# HMI_Board.net
KiCad netlist of a schematic drawn in EAGLE
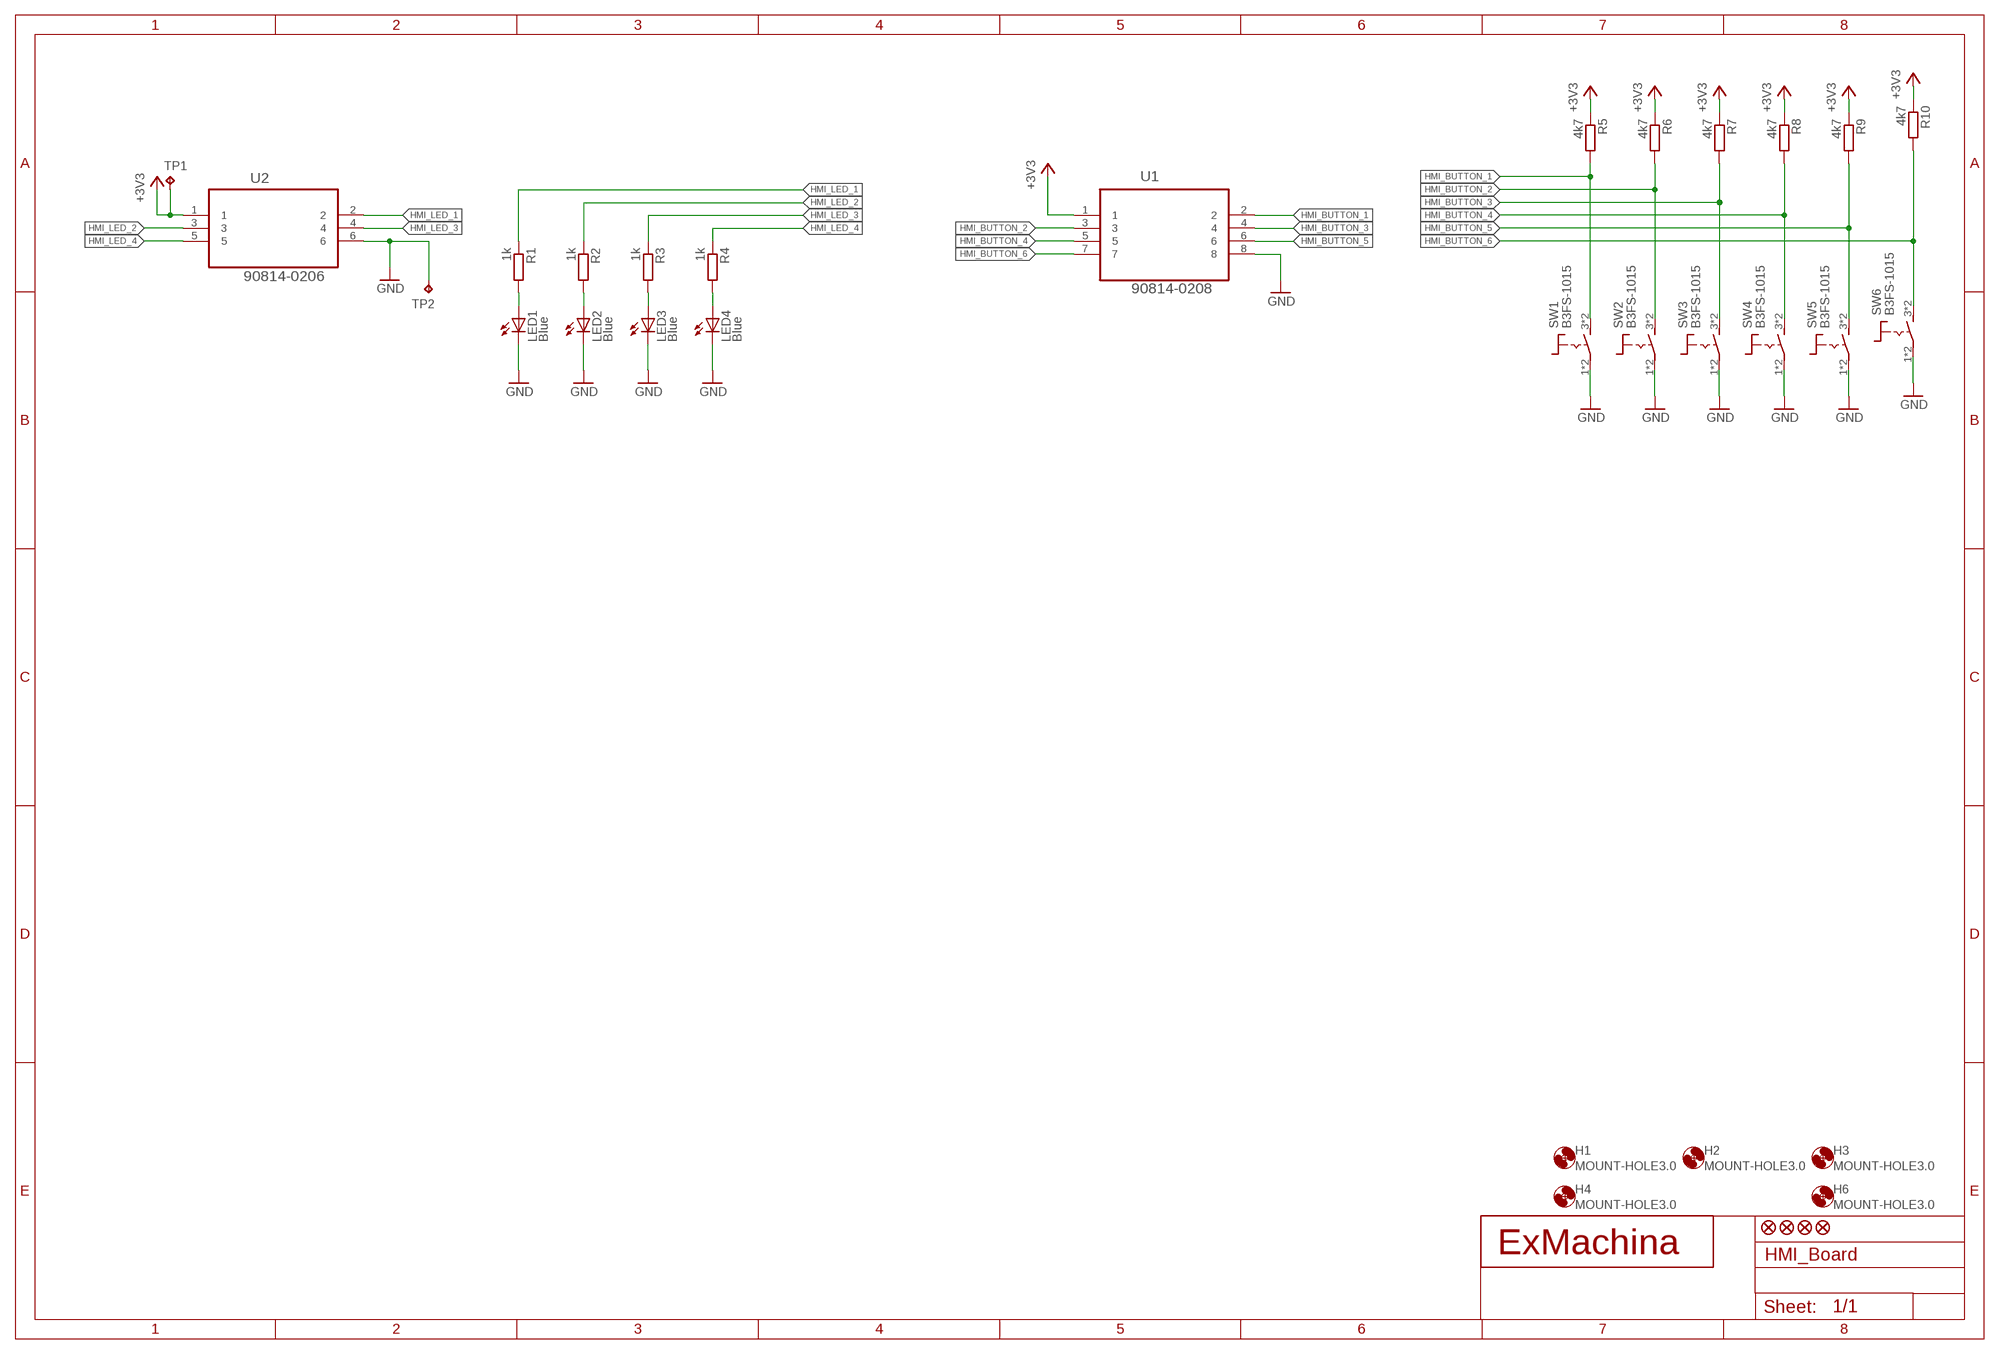
[diagram p0: schematic, sheet 1]

(export (version "E")
  (design (tool "Eeschema 10.0.6"))
  (components
    (comp (ref "H1")
      (value "MOUNT-HOLE3.0")
      (footprint "eagle-import:3,0")
      (libsource (lib "eagle-import") (part "MOUNT-HOLE3.0"))
    )
    (comp (ref "H2")
      (value "MOUNT-HOLE3.0")
      (footprint "eagle-import:3,0")
      (libsource (lib "eagle-import") (part "MOUNT-HOLE3.0"))
    )
    (comp (ref "H3")
      (value "MOUNT-HOLE3.0")
      (footprint "eagle-import:3,0")
      (libsource (lib "eagle-import") (part "MOUNT-HOLE3.0"))
    )
    (comp (ref "H4")
      (value "MOUNT-HOLE3.0")
      (footprint "eagle-import:3,0")
      (libsource (lib "eagle-import") (part "MOUNT-HOLE3.0"))
    )
    (comp (ref "H6")
      (value "MOUNT-HOLE3.0")
      (footprint "eagle-import:3,0")
      (libsource (lib "eagle-import") (part "MOUNT-HOLE3.0"))
    )
    (comp (ref "JP1")
      (value "FIDUCIAL1X2")
      (footprint "eagle-import:FIDUCIAL-1X2")
      (libsource (lib "eagle-import") (part "FIDUCIAL1X2"))
    )
    (comp (ref "JP2")
      (value "FIDUCIAL1X2")
      (footprint "eagle-import:FIDUCIAL-1X2")
      (libsource (lib "eagle-import") (part "FIDUCIAL1X2"))
    )
    (comp (ref "JP3")
      (value "FIDUCIAL1X2")
      (footprint "eagle-import:FIDUCIAL-1X2")
      (libsource (lib "eagle-import") (part "FIDUCIAL1X2"))
    )
    (comp (ref "JP4")
      (value "FIDUCIAL1X2")
      (footprint "eagle-import:FIDUCIAL-1X2")
      (libsource (lib "eagle-import") (part "FIDUCIAL1X2"))
    )
    (comp (ref "LED1")
      (value "Blue")
      (footprint "eagle-import:SML0603")
      (libsource (lib "eagle-import") (part "LEDSML0603"))
    )
    (comp (ref "LED2")
      (value "Blue")
      (footprint "eagle-import:SML0603")
      (libsource (lib "eagle-import") (part "LEDSML0603"))
    )
    (comp (ref "LED3")
      (value "Blue")
      (footprint "eagle-import:SML0603")
      (libsource (lib "eagle-import") (part "LEDSML0603"))
    )
    (comp (ref "LED4")
      (value "Blue")
      (footprint "eagle-import:SML0603")
      (libsource (lib "eagle-import") (part "LEDSML0603"))
    )
    (comp (ref "R1")
      (value "1k")
      (footprint "eagle-import:R0603")
      (libsource (lib "eagle-import") (part "R-EU_R0603"))
    )
    (comp (ref "R2")
      (value "1k")
      (footprint "eagle-import:R0603")
      (libsource (lib "eagle-import") (part "R-EU_R0603"))
    )
    (comp (ref "R3")
      (value "1k")
      (footprint "eagle-import:R0603")
      (libsource (lib "eagle-import") (part "R-EU_R0603"))
    )
    (comp (ref "R4")
      (value "1k")
      (footprint "eagle-import:R0603")
      (libsource (lib "eagle-import") (part "R-EU_R0603"))
    )
    (comp (ref "R5")
      (value "4k7")
      (footprint "eagle-import:R0603")
      (libsource (lib "eagle-import") (part "R-EU_R0603"))
    )
    (comp (ref "R6")
      (value "4k7")
      (footprint "eagle-import:R0603")
      (libsource (lib "eagle-import") (part "R-EU_R0603"))
    )
    (comp (ref "R7")
      (value "4k7")
      (footprint "eagle-import:R0603")
      (libsource (lib "eagle-import") (part "R-EU_R0603"))
    )
    (comp (ref "R8")
      (value "4k7")
      (footprint "eagle-import:R0603")
      (libsource (lib "eagle-import") (part "R-EU_R0603"))
    )
    (comp (ref "R9")
      (value "4k7")
      (footprint "eagle-import:R0603")
      (libsource (lib "eagle-import") (part "R-EU_R0603"))
    )
    (comp (ref "R10")
      (value "4k7")
      (footprint "eagle-import:R0603")
      (libsource (lib "eagle-import") (part "R-EU_R0603"))
    )
    (comp (ref "SW1")
      (value "B3FS-1015")
      (footprint "eagle-import:B3FS")
      (libsource (lib "eagle-import") (part "B3FS-1015"))
    )
    (comp (ref "SW2")
      (value "B3FS-1015")
      (footprint "eagle-import:B3FS")
      (libsource (lib "eagle-import") (part "B3FS-1015"))
    )
    (comp (ref "SW3")
      (value "B3FS-1015")
      (footprint "eagle-import:B3FS")
      (libsource (lib "eagle-import") (part "B3FS-1015"))
    )
    (comp (ref "SW4")
      (value "B3FS-1015")
      (footprint "eagle-import:B3FS")
      (libsource (lib "eagle-import") (part "B3FS-1015"))
    )
    (comp (ref "SW5")
      (value "B3FS-1015")
      (footprint "eagle-import:B3FS")
      (libsource (lib "eagle-import") (part "B3FS-1015"))
    )
    (comp (ref "SW6")
      (value "B3FS-1015")
      (footprint "eagle-import:B3FS")
      (libsource (lib "eagle-import") (part "B3FS-1015"))
    )
    (comp (ref "TP1")
      (value "TPB2,54")
      (footprint "eagle-import:B2,54")
      (libsource (lib "eagle-import") (part "TPB2,54"))
    )
    (comp (ref "TP2")
      (value "TPB2,54")
      (footprint "eagle-import:B2,54")
      (libsource (lib "eagle-import") (part "TPB2,54"))
    )
    (comp (ref "U$1")
      (value "EXMACHINA-LOGO-NAME")
      (footprint "eagle-import:EXM-LOGO-BASELINE")
      (libsource (lib "eagle-import") (part "EXMACHINA-LOGO-NAME"))
    )
    (comp (ref "U1")
      (value "90814-0208")
      (footprint "eagle-import:MOLEX_90814-0208")
      (libsource (lib "eagle-import") (part "90814-0208"))
    )
    (comp (ref "U2")
      (value "90814-0206")
      (footprint "eagle-import:MOLEX_90814-0206")
      (libsource (lib "eagle-import") (part "90814-0206"))
    )
  )
  (nets
    (net (code "1") (name "+3V3") (class "Default")
      (node (ref "R10") (pin "1") (pinfunction "1_1") (pintype "passive"))
      (node (ref "R5") (pin "1") (pinfunction "1_1") (pintype "passive"))
      (node (ref "R6") (pin "1") (pinfunction "1_1") (pintype "passive"))
      (node (ref "R7") (pin "1") (pinfunction "1_1") (pintype "passive"))
      (node (ref "R8") (pin "1") (pinfunction "1_1") (pintype "passive"))
      (node (ref "R9") (pin "1") (pinfunction "1_1") (pintype "passive"))
      (node (ref "TP1") (pin "TP") (pinfunction "TP_TP") (pintype "input"))
      (node (ref "U1") (pin "1") (pinfunction "1_1") (pintype "passive"))
      (node (ref "U2") (pin "1") (pinfunction "1_1") (pintype "passive"))
    )
    (net (code "2") (name "GND") (class "Default")
      (node (ref "LED1") (pin "C") (pinfunction "C_C") (pintype "passive"))
      (node (ref "LED2") (pin "C") (pinfunction "C_C") (pintype "passive"))
      (node (ref "LED3") (pin "C") (pinfunction "C_C") (pintype "passive"))
      (node (ref "LED4") (pin "C") (pinfunction "C_C") (pintype "passive"))
      (node (ref "SW1") (pin "1") (pinfunction "2_1") (pintype "passive"))
      (node (ref "SW1") (pin "2") (pinfunction "2_2") (pintype "passive"))
      (node (ref "SW2") (pin "1") (pinfunction "2_1") (pintype "passive"))
      (node (ref "SW2") (pin "2") (pinfunction "2_2") (pintype "passive"))
      (node (ref "SW3") (pin "1") (pinfunction "2_1") (pintype "passive"))
      (node (ref "SW3") (pin "2") (pinfunction "2_2") (pintype "passive"))
      (node (ref "SW4") (pin "1") (pinfunction "2_1") (pintype "passive"))
      (node (ref "SW4") (pin "2") (pinfunction "2_2") (pintype "passive"))
      (node (ref "SW5") (pin "1") (pinfunction "2_1") (pintype "passive"))
      (node (ref "SW5") (pin "2") (pinfunction "2_2") (pintype "passive"))
      (node (ref "SW6") (pin "1") (pinfunction "2_1") (pintype "passive"))
      (node (ref "SW6") (pin "2") (pinfunction "2_2") (pintype "passive"))
      (node (ref "TP2") (pin "TP") (pinfunction "TP_TP") (pintype "input"))
      (node (ref "U1") (pin "8") (pinfunction "8_8") (pintype "passive"))
      (node (ref "U2") (pin "6") (pinfunction "6_6") (pintype "passive"))
    )
    (net (code "3") (name "HMI_BUTTON_1") (class "Default")
      (node (ref "R5") (pin "2") (pinfunction "2_2") (pintype "passive"))
      (node (ref "SW1") (pin "3") (pinfunction "1_3") (pintype "passive"))
      (node (ref "SW1") (pin "4") (pinfunction "1_4") (pintype "passive"))
      (node (ref "U1") (pin "2") (pinfunction "2_2") (pintype "passive"))
    )
    (net (code "4") (name "HMI_BUTTON_2") (class "Default")
      (node (ref "R6") (pin "2") (pinfunction "2_2") (pintype "passive"))
      (node (ref "SW2") (pin "3") (pinfunction "1_3") (pintype "passive"))
      (node (ref "SW2") (pin "4") (pinfunction "1_4") (pintype "passive"))
      (node (ref "U1") (pin "3") (pinfunction "3_3") (pintype "passive"))
    )
    (net (code "5") (name "HMI_BUTTON_3") (class "Default")
      (node (ref "R7") (pin "2") (pinfunction "2_2") (pintype "passive"))
      (node (ref "SW3") (pin "3") (pinfunction "1_3") (pintype "passive"))
      (node (ref "SW3") (pin "4") (pinfunction "1_4") (pintype "passive"))
      (node (ref "U1") (pin "4") (pinfunction "4_4") (pintype "passive"))
    )
    (net (code "6") (name "HMI_BUTTON_4") (class "Default")
      (node (ref "R8") (pin "2") (pinfunction "2_2") (pintype "passive"))
      (node (ref "SW4") (pin "3") (pinfunction "1_3") (pintype "passive"))
      (node (ref "SW4") (pin "4") (pinfunction "1_4") (pintype "passive"))
      (node (ref "U1") (pin "5") (pinfunction "5_5") (pintype "passive"))
    )
    (net (code "7") (name "HMI_BUTTON_5") (class "Default")
      (node (ref "R9") (pin "2") (pinfunction "2_2") (pintype "passive"))
      (node (ref "SW5") (pin "3") (pinfunction "1_3") (pintype "passive"))
      (node (ref "SW5") (pin "4") (pinfunction "1_4") (pintype "passive"))
      (node (ref "U1") (pin "6") (pinfunction "6_6") (pintype "passive"))
    )
    (net (code "8") (name "HMI_BUTTON_6") (class "Default")
      (node (ref "R10") (pin "2") (pinfunction "2_2") (pintype "passive"))
      (node (ref "SW6") (pin "3") (pinfunction "1_3") (pintype "passive"))
      (node (ref "SW6") (pin "4") (pinfunction "1_4") (pintype "passive"))
      (node (ref "U1") (pin "7") (pinfunction "7_7") (pintype "passive"))
    )
    (net (code "9") (name "HMI_LED_1") (class "Default")
      (node (ref "R1") (pin "1") (pinfunction "1_1") (pintype "passive"))
      (node (ref "U2") (pin "2") (pinfunction "2_2") (pintype "passive"))
    )
    (net (code "10") (name "HMI_LED_2") (class "Default")
      (node (ref "R2") (pin "1") (pinfunction "1_1") (pintype "passive"))
      (node (ref "U2") (pin "3") (pinfunction "3_3") (pintype "passive"))
    )
    (net (code "11") (name "HMI_LED_3") (class "Default")
      (node (ref "R3") (pin "1") (pinfunction "1_1") (pintype "passive"))
      (node (ref "U2") (pin "4") (pinfunction "4_4") (pintype "passive"))
    )
    (net (code "12") (name "HMI_LED_4") (class "Default")
      (node (ref "R4") (pin "1") (pinfunction "1_1") (pintype "passive"))
      (node (ref "U2") (pin "5") (pinfunction "5_5") (pintype "passive"))
    )
    (net (code "13") (name "Net-(LED1-PadA)") (class "Default")
      (node (ref "LED1") (pin "A") (pinfunction "A_A") (pintype "passive"))
      (node (ref "R1") (pin "2") (pinfunction "2_2") (pintype "passive"))
    )
    (net (code "14") (name "Net-(LED2-PadA)") (class "Default")
      (node (ref "LED2") (pin "A") (pinfunction "A_A") (pintype "passive"))
      (node (ref "R2") (pin "2") (pinfunction "2_2") (pintype "passive"))
    )
    (net (code "15") (name "Net-(LED3-PadA)") (class "Default")
      (node (ref "LED3") (pin "A") (pinfunction "A_A") (pintype "passive"))
      (node (ref "R3") (pin "2") (pinfunction "2_2") (pintype "passive"))
    )
    (net (code "16") (name "Net-(LED4-PadA)") (class "Default")
      (node (ref "LED4") (pin "A") (pinfunction "A_A") (pintype "passive"))
      (node (ref "R4") (pin "2") (pinfunction "2_2") (pintype "passive"))
    )
  )
)
